# untitled.net
KiCad netlist of a schematic drawn in EAGLE
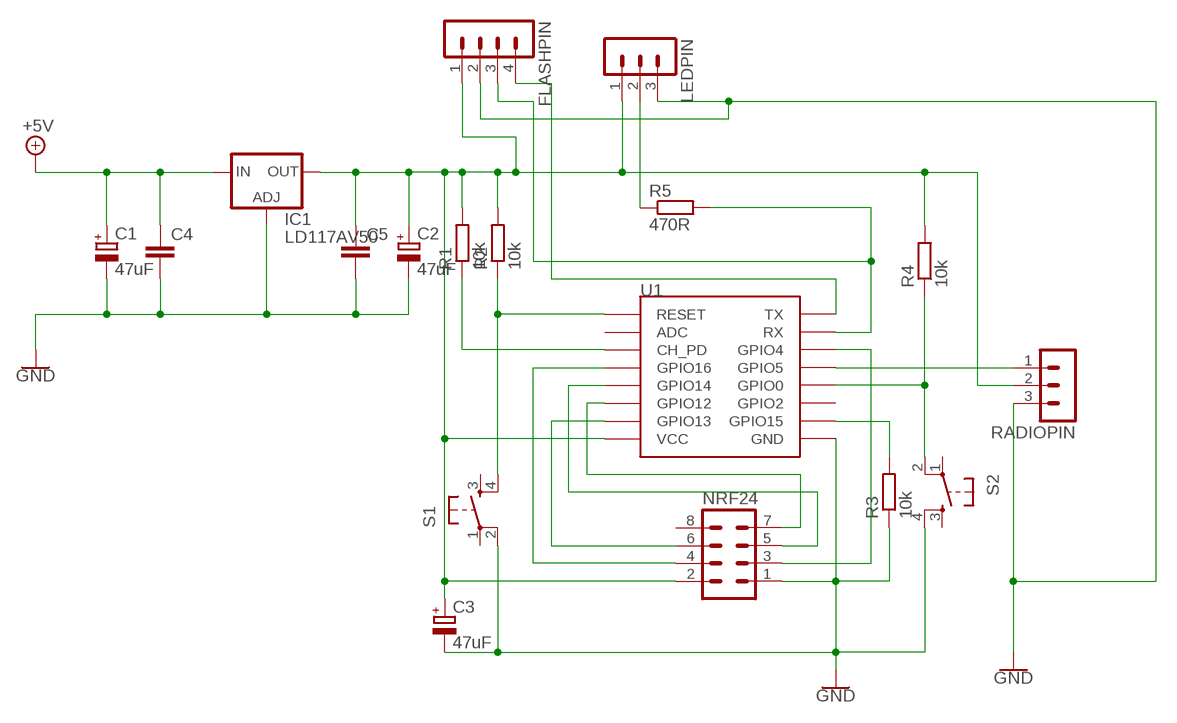
[diagram p0: schematic, sheet 1]

(export (version "E")
  (design (tool "Eeschema 10.0.6"))
  (components
    (comp (ref "C1")
      (value "47uF")
      (footprint "eagle-import:E2-5")
      (libsource (lib "eagle-import") (part "CPOL-EUE2-5"))
    )
    (comp (ref "C2")
      (value "47uF")
      (footprint "eagle-import:E2-5")
      (libsource (lib "eagle-import") (part "CPOL-EUE2-5"))
    )
    (comp (ref "C3")
      (value "47uF")
      (footprint "eagle-import:E2-5")
      (libsource (lib "eagle-import") (part "CPOL-EUE2-5"))
    )
    (comp (ref "C4")
      (value "C-EU025-025X050")
      (footprint "eagle-import:C025-025X050")
      (libsource (lib "eagle-import") (part "C-EU025-025X050"))
    )
    (comp (ref "C5")
      (value "C-EU025-025X050")
      (footprint "eagle-import:C025-025X050")
      (libsource (lib "eagle-import") (part "C-EU025-025X050"))
    )
    (comp (ref "FLASHPIN")
      (value "MA04-1")
      (footprint "eagle-import:MA04-1")
      (libsource (lib "eagle-import") (part "MA04-1"))
    )
    (comp (ref "IC1")
      (value "LD117AV50")
      (footprint "eagle-import:TO220L1")
      (libsource (lib "eagle-import") (part "LD117A?V50"))
    )
    (comp (ref "LEDPIN")
      (value "MA03-1")
      (footprint "eagle-import:MA03-1")
      (libsource (lib "eagle-import") (part "MA03-1"))
    )
    (comp (ref "NRF24")
      (value "MA04-2")
      (footprint "eagle-import:MA04-2")
      (libsource (lib "eagle-import") (part "MA04-2"))
    )
    (comp (ref "R1")
      (value "10k")
      (footprint "eagle-import:0207_10")
      (libsource (lib "eagle-import") (part "R-EU_0207/10"))
    )
    (comp (ref "R2")
      (value "10k")
      (footprint "eagle-import:0207_10")
      (libsource (lib "eagle-import") (part "R-EU_0207/10"))
    )
    (comp (ref "R3")
      (value "10k")
      (footprint "eagle-import:0207_10")
      (libsource (lib "eagle-import") (part "R-EU_0207/10"))
    )
    (comp (ref "R4")
      (value "10k")
      (footprint "eagle-import:0207_10")
      (libsource (lib "eagle-import") (part "R-EU_0207/10"))
    )
    (comp (ref "R5")
      (value "470R")
      (footprint "eagle-import:0207_10")
      (libsource (lib "eagle-import") (part "R-EU_0207/10"))
    )
    (comp (ref "RADIOPIN")
      (value "MA03-1")
      (footprint "eagle-import:MA03-1")
      (libsource (lib "eagle-import") (part "MA03-1"))
    )
    (comp (ref "S1")
      (value "TAC_SWITCHPTH")
      (footprint "eagle-import:TACTILE-PTH")
      (libsource (lib "eagle-import") (part "TAC_SWITCHPTH"))
    )
    (comp (ref "S2")
      (value "TAC_SWITCHPTH")
      (footprint "eagle-import:TACTILE-PTH")
      (libsource (lib "eagle-import") (part "TAC_SWITCHPTH"))
    )
    (comp (ref "U1")
      (value "ESP12")
      (footprint "eagle-import:ESP12")
      (libsource (lib "eagle-import") (part "ESP12"))
    )
  )
  (nets
    (net (code "1") (name "+5V") (class "Default")
      (node (ref "C1") (pin "+") (pinfunction "+_+") (pintype "passive"))
      (node (ref "C4") (pin "1") (pinfunction "1_1") (pintype "passive"))
      (node (ref "IC1") (pin "3") (pinfunction "IN_3") (pintype "input"))
    )
    (net (code "2") (name "GND") (class "Default")
      (node (ref "C1") (pin "-") (pinfunction "-_-") (pintype "passive"))
      (node (ref "C2") (pin "-") (pinfunction "-_-") (pintype "passive"))
      (node (ref "C3") (pin "-") (pinfunction "-_-") (pintype "passive"))
      (node (ref "C4") (pin "2") (pinfunction "2_2") (pintype "passive"))
      (node (ref "C5") (pin "2") (pinfunction "2_2") (pintype "passive"))
      (node (ref "FLASHPIN") (pin "2") (pinfunction "2_2") (pintype "passive"))
      (node (ref "IC1") (pin "1") (pinfunction "ADJ_1") (pintype "input"))
      (node (ref "LEDPIN") (pin "3") (pinfunction "3_3") (pintype "passive"))
      (node (ref "NRF24") (pin "1") (pinfunction "1_1") (pintype "passive"))
      (node (ref "R3") (pin "1") (pinfunction "1_1") (pintype "passive"))
      (node (ref "RADIOPIN") (pin "3") (pinfunction "3_3") (pintype "passive"))
      (node (ref "S1") (pin "2") (pinfunction "2_2") (pintype "passive"))
      (node (ref "S2") (pin "4") (pinfunction "4_4") (pintype "passive"))
      (node (ref "U1") (pin "GND") (pinfunction "GND_GND") (pintype "bidirectional"))
    )
    (net (code "3") (name "Net-(FLASHPIN-Pad3)") (class "Default")
      (node (ref "FLASHPIN") (pin "3") (pinfunction "3_3") (pintype "passive"))
      (node (ref "R5") (pin "2") (pinfunction "2_2") (pintype "passive"))
      (node (ref "U1") (pin "RX") (pinfunction "RX_RX") (pintype "bidirectional"))
    )
    (net (code "4") (name "Net-(FLASHPIN-Pad4)") (class "Default")
      (node (ref "FLASHPIN") (pin "4") (pinfunction "4_4") (pintype "passive"))
      (node (ref "U1") (pin "TX") (pinfunction "TX_TX") (pintype "bidirectional"))
    )
    (net (code "5") (name "Net-(IC1-OUT)") (class "Default")
      (node (ref "C2") (pin "+") (pinfunction "+_+") (pintype "passive"))
      (node (ref "C3") (pin "+") (pinfunction "+_+") (pintype "passive"))
      (node (ref "C5") (pin "1") (pinfunction "1_1") (pintype "passive"))
      (node (ref "FLASHPIN") (pin "1") (pinfunction "1_1") (pintype "passive"))
      (node (ref "IC1") (pin "2") (pinfunction "OUT_2") (pintype "passive"))
      (node (ref "LEDPIN") (pin "1") (pinfunction "1_1") (pintype "passive"))
      (node (ref "NRF24") (pin "2") (pinfunction "2_2") (pintype "passive"))
      (node (ref "R1") (pin "2") (pinfunction "2_2") (pintype "passive"))
      (node (ref "R2") (pin "2") (pinfunction "2_2") (pintype "passive"))
      (node (ref "R4") (pin "2") (pinfunction "2_2") (pintype "passive"))
      (node (ref "RADIOPIN") (pin "2") (pinfunction "2_2") (pintype "passive"))
      (node (ref "U1") (pin "VCC") (pinfunction "VCC_VCC") (pintype "bidirectional"))
    )
    (net (code "6") (name "Net-(LEDPIN-Pad2)") (class "Default")
      (node (ref "LEDPIN") (pin "2") (pinfunction "2_2") (pintype "passive"))
      (node (ref "R5") (pin "1") (pinfunction "1_1") (pintype "passive"))
    )
    (net (code "7") (name "Net-(NRF24-Pad3)") (class "Default")
      (node (ref "NRF24") (pin "3") (pinfunction "3_3") (pintype "passive"))
      (node (ref "U1") (pin "GPIO4") (pinfunction "GPIO4_GPIO4") (pintype "bidirectional"))
    )
    (net (code "8") (name "Net-(NRF24-Pad4)") (class "Default")
      (node (ref "NRF24") (pin "4") (pinfunction "4_4") (pintype "passive"))
      (node (ref "U1") (pin "GPIO16") (pinfunction "GPIO16_GPIO16") (pintype "bidirectional"))
    )
    (net (code "9") (name "Net-(NRF24-Pad5)") (class "Default")
      (node (ref "NRF24") (pin "5") (pinfunction "5_5") (pintype "passive"))
      (node (ref "U1") (pin "GPIO14") (pinfunction "GPIO14_GPIO14") (pintype "bidirectional"))
    )
    (net (code "10") (name "Net-(NRF24-Pad6)") (class "Default")
      (node (ref "NRF24") (pin "6") (pinfunction "6_6") (pintype "passive"))
      (node (ref "U1") (pin "GPIO13") (pinfunction "GPIO13_GPIO13") (pintype "bidirectional"))
    )
    (net (code "11") (name "Net-(NRF24-Pad7)") (class "Default")
      (node (ref "NRF24") (pin "7") (pinfunction "7_7") (pintype "passive"))
      (node (ref "U1") (pin "GPIO12") (pinfunction "GPIO12_GPIO12") (pintype "bidirectional"))
    )
    (net (code "12") (name "Net-(R1-Pad1)") (class "Default")
      (node (ref "R1") (pin "1") (pinfunction "1_1") (pintype "passive"))
      (node (ref "U1") (pin "CH_PD") (pinfunction "CH_PD_CH_PD") (pintype "bidirectional"))
    )
    (net (code "13") (name "Net-(R2-Pad1)") (class "Default")
      (node (ref "R2") (pin "1") (pinfunction "1_1") (pintype "passive"))
      (node (ref "S1") (pin "4") (pinfunction "4_4") (pintype "passive"))
      (node (ref "U1") (pin "RESET") (pinfunction "RESET_RESET") (pintype "bidirectional"))
    )
    (net (code "14") (name "Net-(R3-Pad2)") (class "Default")
      (node (ref "R3") (pin "2") (pinfunction "2_2") (pintype "passive"))
      (node (ref "U1") (pin "GPIO15") (pinfunction "GPIO15_GPIO15") (pintype "bidirectional"))
    )
    (net (code "15") (name "Net-(R4-Pad1)") (class "Default")
      (node (ref "R4") (pin "1") (pinfunction "1_1") (pintype "passive"))
      (node (ref "S2") (pin "2") (pinfunction "2_2") (pintype "passive"))
      (node (ref "U1") (pin "GPIO0") (pinfunction "GPIO0_GPIO0") (pintype "bidirectional"))
    )
    (net (code "16") (name "Net-(RADIOPIN-Pad1)") (class "Default")
      (node (ref "RADIOPIN") (pin "1") (pinfunction "1_1") (pintype "passive"))
      (node (ref "U1") (pin "GPIO5") (pinfunction "GPIO5_GPIO5") (pintype "bidirectional"))
    )
    (net (code "17") (name "unconnected-(NRF24-Pad8)") (class "Default")
      (node (ref "NRF24") (pin "8") (pinfunction "8_8") (pintype "passive"))
    )
    (net (code "18") (name "unconnected-(S1-Pad1)") (class "Default")
      (node (ref "S1") (pin "1") (pinfunction "1_1") (pintype "passive"))
    )
    (net (code "19") (name "unconnected-(S1-Pad3)") (class "Default")
      (node (ref "S1") (pin "3") (pinfunction "3_3") (pintype "passive"))
    )
    (net (code "20") (name "unconnected-(S2-Pad1)") (class "Default")
      (node (ref "S2") (pin "1") (pinfunction "1_1") (pintype "passive"))
    )
    (net (code "21") (name "unconnected-(S2-Pad3)") (class "Default")
      (node (ref "S2") (pin "3") (pinfunction "3_3") (pintype "passive"))
    )
    (net (code "22") (name "unconnected-(U1-PadADC)") (class "Default")
      (node (ref "U1") (pin "ADC") (pinfunction "ADC_ADC") (pintype "bidirectional"))
    )
    (net (code "23") (name "unconnected-(U1-PadGPIO2)") (class "Default")
      (node (ref "U1") (pin "GPIO2") (pinfunction "GPIO2_GPIO2") (pintype "bidirectional"))
    )
  )
)
